# breakout_pmg001.net
KiCad netlist of a schematic drawn in EAGLE
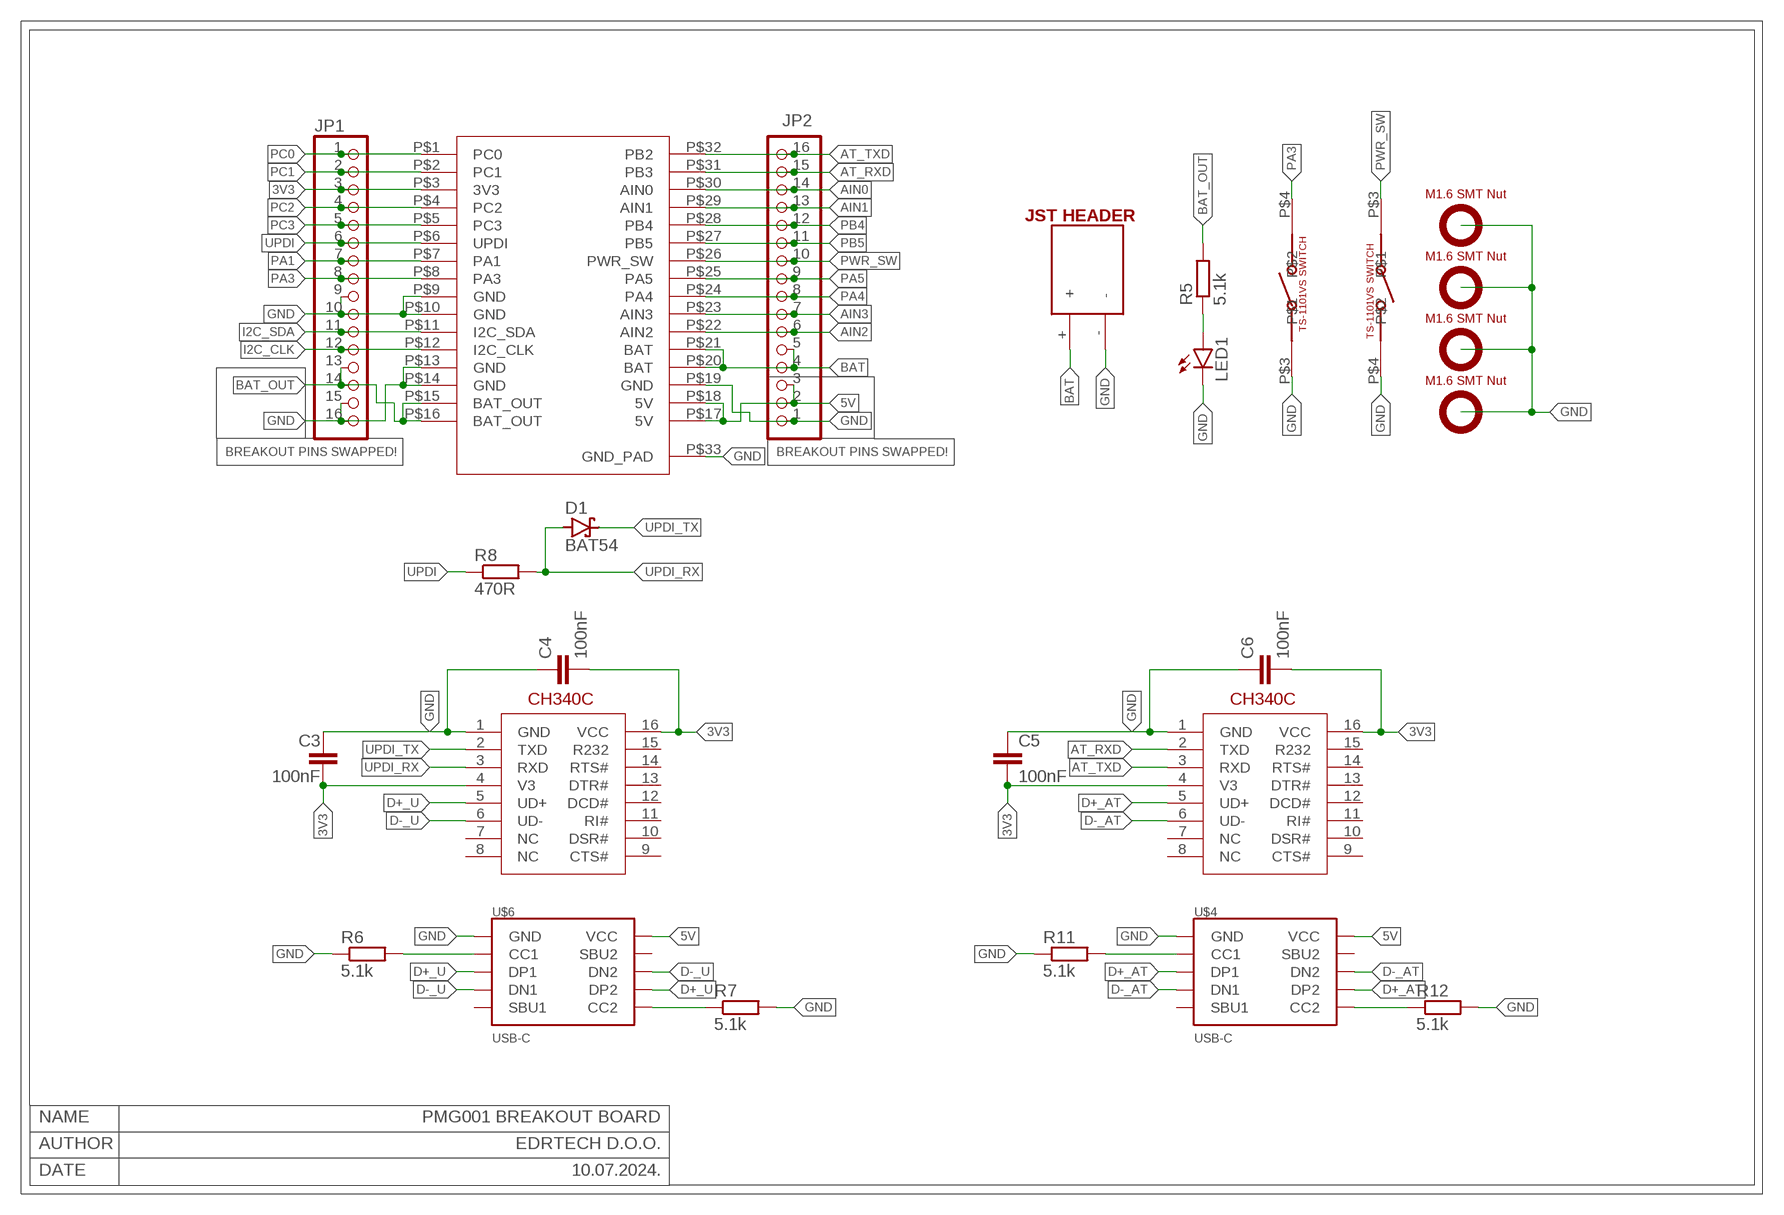
[diagram p0: schematic, sheet 1]

(export (version "E")
  (design (tool "Eeschema 10.0.6"))
  (components
    (comp (ref "C3")
      (value "100nF")
      (footprint "eagle-import:C0603")
      (libsource (lib "eagle-import") (part "CC0603"))
    )
    (comp (ref "C4")
      (value "100nF")
      (footprint "eagle-import:C0603")
      (libsource (lib "eagle-import") (part "CC0603"))
    )
    (comp (ref "C5")
      (value "100nF")
      (footprint "eagle-import:C0603")
      (libsource (lib "eagle-import") (part "CC0603"))
    )
    (comp (ref "C6")
      (value "100nF")
      (footprint "eagle-import:C0603")
      (libsource (lib "eagle-import") (part "CC0603"))
    )
    (comp (ref "D1")
      (value "BAT54")
      (footprint "eagle-import:SOT23")
      (libsource (lib "eagle-import") (part "BAT54"))
    )
    (comp (ref "JP1")
      (value "PINHD-1X16")
      (footprint "eagle-import:1X16")
      (libsource (lib "eagle-import") (part "PINHD-1X16"))
    )
    (comp (ref "JP2")
      (value "PINHD-1X16")
      (footprint "eagle-import:1X16")
      (libsource (lib "eagle-import") (part "PINHD-1X16"))
    )
    (comp (ref "LED1")
      (value "LEDCHIPLED_1206")
      (footprint "eagle-import:CHIPLED_1206")
      (libsource (lib "eagle-import") (part "LEDCHIPLED_1206"))
    )
    (comp (ref "R5")
      (value "5.1k")
      (footprint "eagle-import:R0603")
      (libsource (lib "eagle-import") (part "R-EU_R0603"))
    )
    (comp (ref "R6")
      (value "5.1k")
      (footprint "eagle-import:R0603")
      (libsource (lib "eagle-import") (part "R-EU_R0603"))
    )
    (comp (ref "R7")
      (value "5.1k")
      (footprint "eagle-import:R0603")
      (libsource (lib "eagle-import") (part "R-EU_R0603"))
    )
    (comp (ref "R8")
      (value "470R")
      (footprint "eagle-import:R0603")
      (libsource (lib "eagle-import") (part "R-EU_R0603"))
    )
    (comp (ref "R11")
      (value "5.1k")
      (footprint "eagle-import:R0603")
      (libsource (lib "eagle-import") (part "R-EU_R0603"))
    )
    (comp (ref "R12")
      (value "5.1k")
      (footprint "eagle-import:R0603")
      (libsource (lib "eagle-import") (part "R-EU_R0603"))
    )
    (comp (ref "SPEAKER_CON1")
      (value "JST_HEADER_2MM_2P")
      (footprint "eagle-import:JST_HEADER")
      (libsource (lib "eagle-import") (part "JST_HEADER_2MM_2P"))
    )
    (comp (ref "U$1")
      (value "CH340C")
      (footprint "eagle-import:CH340C")
      (libsource (lib "eagle-import") (part "CH340C"))
    )
    (comp (ref "U$2")
      (value "TS-1101VS-C-A-A")
      (footprint "eagle-import:TS-1101VS-C-A-A")
      (libsource (lib "eagle-import") (part "TS-1101VS-C-A-A"))
    )
    (comp (ref "U$3")
      (value "TS-1101VS-C-A-A")
      (footprint "eagle-import:TS-1101VS-C-A-A")
      (libsource (lib "eagle-import") (part "TS-1101VS-C-A-A"))
    )
    (comp (ref "U$4")
      (value "USB-C")
      (footprint "eagle-import:USB-C")
      (libsource (lib "eagle-import") (part "USB-C"))
    )
    (comp (ref "U$5")
      (value "CH340C")
      (footprint "eagle-import:CH340C")
      (libsource (lib "eagle-import") (part "CH340C"))
    )
    (comp (ref "U$6")
      (value "USB-C")
      (footprint "eagle-import:USB-C")
      (libsource (lib "eagle-import") (part "USB-C"))
    )
    (comp (ref "U$7")
      (value "PMG001")
      (footprint "eagle-import:PMG001")
      (libsource (lib "eagle-import") (part "PMG001"))
    )
    (comp (ref "U$8")
      (value "SMTSO16")
      (footprint "eagle-import:SMTSO16")
      (libsource (lib "eagle-import") (part "SMTSO16"))
    )
    (comp (ref "U$9")
      (value "SMTSO16")
      (footprint "eagle-import:SMTSO16")
      (libsource (lib "eagle-import") (part "SMTSO16"))
    )
    (comp (ref "U$10")
      (value "SMTSO16")
      (footprint "eagle-import:SMTSO16")
      (libsource (lib "eagle-import") (part "SMTSO16"))
    )
    (comp (ref "U$11")
      (value "SMTSO16")
      (footprint "eagle-import:SMTSO16")
      (libsource (lib "eagle-import") (part "SMTSO16"))
    )
  )
  (nets
    (net (code "1") (name "3V3") (class "Default")
      (node (ref "C3") (pin "2") (pinfunction "2_2") (pintype "passive"))
      (node (ref "C4") (pin "2") (pinfunction "2_2") (pintype "passive"))
      (node (ref "C5") (pin "2") (pinfunction "2_2") (pintype "passive"))
      (node (ref "C6") (pin "2") (pinfunction "2_2") (pintype "passive"))
      (node (ref "JP1") (pin "3") (pinfunction "3_3") (pintype "passive"))
      (node (ref "U$1") (pin "16") (pinfunction "VCC_16") (pintype "bidirectional"))
      (node (ref "U$1") (pin "4") (pinfunction "V3_4") (pintype "bidirectional"))
      (node (ref "U$5") (pin "16") (pinfunction "VCC_16") (pintype "bidirectional"))
      (node (ref "U$5") (pin "4") (pinfunction "V3_4") (pintype "bidirectional"))
      (node (ref "U$7") (pin "P$3") (pinfunction "3V3_P$3") (pintype "bidirectional"))
    )
    (net (code "2") (name "5V") (class "Default")
      (node (ref "JP2") (pin "2") (pinfunction "2_2") (pintype "passive"))
      (node (ref "JP2") (pin "3") (pinfunction "3_3") (pintype "passive"))
      (node (ref "U$4") (pin "VCC@1") (pinfunction "VCC_VCC@1") (pintype "bidirectional"))
      (node (ref "U$4") (pin "VCC@2") (pinfunction "VCC_VCC@2") (pintype "bidirectional"))
      (node (ref "U$6") (pin "VCC@1") (pinfunction "VCC_VCC@1") (pintype "bidirectional"))
      (node (ref "U$6") (pin "VCC@2") (pinfunction "VCC_VCC@2") (pintype "bidirectional"))
      (node (ref "U$7") (pin "P$17") (pinfunction "5V_P$17") (pintype "bidirectional"))
      (node (ref "U$7") (pin "P$18") (pinfunction "5V_P$18") (pintype "bidirectional"))
    )
    (net (code "3") (name "AIN0") (class "Default")
      (node (ref "JP2") (pin "14") (pinfunction "14_14") (pintype "passive"))
      (node (ref "U$7") (pin "P$30") (pinfunction "AIN0_P$30") (pintype "bidirectional"))
    )
    (net (code "4") (name "AIN1") (class "Default")
      (node (ref "JP2") (pin "13") (pinfunction "13_13") (pintype "passive"))
      (node (ref "U$7") (pin "P$29") (pinfunction "AIN1_P$29") (pintype "bidirectional"))
    )
    (net (code "5") (name "AIN2") (class "Default")
      (node (ref "JP2") (pin "6") (pinfunction "6_6") (pintype "passive"))
      (node (ref "U$7") (pin "P$22") (pinfunction "AIN2_P$22") (pintype "bidirectional"))
    )
    (net (code "6") (name "AIN3") (class "Default")
      (node (ref "JP2") (pin "7") (pinfunction "7_7") (pintype "passive"))
      (node (ref "U$7") (pin "P$23") (pinfunction "AIN3_P$23") (pintype "bidirectional"))
    )
    (net (code "7") (name "AT_RXD") (class "Default")
      (node (ref "JP2") (pin "15") (pinfunction "15_15") (pintype "passive"))
      (node (ref "U$1") (pin "2") (pinfunction "TXD_2") (pintype "bidirectional"))
      (node (ref "U$7") (pin "P$31") (pinfunction "PB3_P$31") (pintype "bidirectional"))
    )
    (net (code "8") (name "AT_TXD") (class "Default")
      (node (ref "JP2") (pin "16") (pinfunction "16_16") (pintype "passive"))
      (node (ref "U$1") (pin "3") (pinfunction "RXD_3") (pintype "bidirectional"))
      (node (ref "U$7") (pin "P$32") (pinfunction "PB2_P$32") (pintype "bidirectional"))
    )
    (net (code "9") (name "BAT") (class "Default")
      (node (ref "JP2") (pin "4") (pinfunction "4_4") (pintype "passive"))
      (node (ref "JP2") (pin "5") (pinfunction "5_5") (pintype "passive"))
      (node (ref "SPEAKER_CON1") (pin "+") (pinfunction "+_+") (pintype "bidirectional"))
      (node (ref "U$7") (pin "P$20") (pinfunction "BAT_P$20") (pintype "bidirectional"))
      (node (ref "U$7") (pin "P$21") (pinfunction "BAT_P$21") (pintype "bidirectional"))
    )
    (net (code "10") (name "BAT_OUT") (class "Default")
      (node (ref "JP1") (pin "13") (pinfunction "13_13") (pintype "passive"))
      (node (ref "JP1") (pin "14") (pinfunction "14_14") (pintype "passive"))
      (node (ref "R5") (pin "2") (pinfunction "2_2") (pintype "passive"))
      (node (ref "U$7") (pin "P$15") (pinfunction "BAT_OUT_P$15") (pintype "bidirectional"))
      (node (ref "U$7") (pin "P$16") (pinfunction "BAT_OUT_P$16") (pintype "bidirectional"))
    )
    (net (code "11") (name "D+_AT") (class "Default")
      (node (ref "U$1") (pin "5") (pinfunction "UD+_5") (pintype "bidirectional"))
      (node (ref "U$4") (pin "DP1") (pinfunction "DP1_DP1") (pintype "bidirectional"))
      (node (ref "U$4") (pin "DP2") (pinfunction "DP2_DP2") (pintype "bidirectional"))
    )
    (net (code "12") (name "D+_U") (class "Default")
      (node (ref "U$5") (pin "5") (pinfunction "UD+_5") (pintype "bidirectional"))
      (node (ref "U$6") (pin "DP1") (pinfunction "DP1_DP1") (pintype "bidirectional"))
      (node (ref "U$6") (pin "DP2") (pinfunction "DP2_DP2") (pintype "bidirectional"))
    )
    (net (code "13") (name "D-_AT") (class "Default")
      (node (ref "U$1") (pin "6") (pinfunction "UD-_6") (pintype "bidirectional"))
      (node (ref "U$4") (pin "DN1") (pinfunction "DN1_DN1") (pintype "bidirectional"))
      (node (ref "U$4") (pin "DN2") (pinfunction "DN2_DN2") (pintype "bidirectional"))
    )
    (net (code "14") (name "D-_U") (class "Default")
      (node (ref "U$5") (pin "6") (pinfunction "UD-_6") (pintype "bidirectional"))
      (node (ref "U$6") (pin "DN1") (pinfunction "DN1_DN1") (pintype "bidirectional"))
      (node (ref "U$6") (pin "DN2") (pinfunction "DN2_DN2") (pintype "bidirectional"))
    )
    (net (code "15") (name "GND") (class "Default")
      (node (ref "C3") (pin "1") (pinfunction "1_1") (pintype "passive"))
      (node (ref "C4") (pin "1") (pinfunction "1_1") (pintype "passive"))
      (node (ref "C5") (pin "1") (pinfunction "1_1") (pintype "passive"))
      (node (ref "C6") (pin "1") (pinfunction "1_1") (pintype "passive"))
      (node (ref "JP1") (pin "10") (pinfunction "10_10") (pintype "passive"))
      (node (ref "JP1") (pin "15") (pinfunction "15_15") (pintype "passive"))
      (node (ref "JP1") (pin "16") (pinfunction "16_16") (pintype "passive"))
      (node (ref "JP1") (pin "9") (pinfunction "9_9") (pintype "passive"))
      (node (ref "JP2") (pin "1") (pinfunction "1_1") (pintype "passive"))
      (node (ref "LED1") (pin "C") (pinfunction "C_C") (pintype "passive"))
      (node (ref "R11") (pin "1") (pinfunction "1_1") (pintype "passive"))
      (node (ref "R12") (pin "2") (pinfunction "2_2") (pintype "passive"))
      (node (ref "R6") (pin "1") (pinfunction "1_1") (pintype "passive"))
      (node (ref "R7") (pin "2") (pinfunction "2_2") (pintype "passive"))
      (node (ref "SPEAKER_CON1") (pin "-") (pinfunction "-_-") (pintype "bidirectional"))
      (node (ref "U$1") (pin "1") (pinfunction "GND_1") (pintype "bidirectional"))
      (node (ref "U$10") (pin "P$1") (pinfunction "P$1_P$1") (pintype "bidirectional"))
      (node (ref "U$11") (pin "P$1") (pinfunction "P$1_P$1") (pintype "bidirectional"))
      (node (ref "U$2") (pin "P$3") (pinfunction "P$1_P$3") (pintype "bidirectional"))
      (node (ref "U$3") (pin "P$4") (pinfunction "P$2_P$4") (pintype "bidirectional"))
      (node (ref "U$4") (pin "GND@1") (pinfunction "GND_GND@1") (pintype "bidirectional"))
      (node (ref "U$4") (pin "GND@2") (pinfunction "GND_GND@2") (pintype "bidirectional"))
      (node (ref "U$4") (pin "P$1") (pinfunction "GND_P$1") (pintype "bidirectional"))
      (node (ref "U$4") (pin "P$2") (pinfunction "GND_P$2") (pintype "bidirectional"))
      (node (ref "U$4") (pin "P$3") (pinfunction "GND_P$3") (pintype "bidirectional"))
      (node (ref "U$4") (pin "P$4") (pinfunction "GND_P$4") (pintype "bidirectional"))
      (node (ref "U$5") (pin "1") (pinfunction "GND_1") (pintype "bidirectional"))
      (node (ref "U$6") (pin "GND@1") (pinfunction "GND_GND@1") (pintype "bidirectional"))
      (node (ref "U$6") (pin "GND@2") (pinfunction "GND_GND@2") (pintype "bidirectional"))
      (node (ref "U$6") (pin "P$1") (pinfunction "GND_P$1") (pintype "bidirectional"))
      (node (ref "U$6") (pin "P$2") (pinfunction "GND_P$2") (pintype "bidirectional"))
      (node (ref "U$6") (pin "P$3") (pinfunction "GND_P$3") (pintype "bidirectional"))
      (node (ref "U$6") (pin "P$4") (pinfunction "GND_P$4") (pintype "bidirectional"))
      (node (ref "U$7") (pin "P$10") (pinfunction "GND_P$10") (pintype "bidirectional"))
      (node (ref "U$7") (pin "P$13") (pinfunction "GND_P$13") (pintype "bidirectional"))
      (node (ref "U$7") (pin "P$14") (pinfunction "GND_P$14") (pintype "bidirectional"))
      (node (ref "U$7") (pin "P$19") (pinfunction "GND_P$19") (pintype "bidirectional"))
      (node (ref "U$7") (pin "P$33") (pinfunction "GND_PAD_P$33") (pintype "bidirectional"))
      (node (ref "U$7") (pin "P$9") (pinfunction "GND_P$9") (pintype "bidirectional"))
      (node (ref "U$8") (pin "P$1") (pinfunction "P$1_P$1") (pintype "bidirectional"))
      (node (ref "U$9") (pin "P$1") (pinfunction "P$1_P$1") (pintype "bidirectional"))
    )
    (net (code "16") (name "I2C_CLK") (class "Default")
      (node (ref "JP1") (pin "12") (pinfunction "12_12") (pintype "passive"))
      (node (ref "U$7") (pin "P$12") (pinfunction "I2C_CLK_P$12") (pintype "bidirectional"))
    )
    (net (code "17") (name "I2C_SDA") (class "Default")
      (node (ref "JP1") (pin "11") (pinfunction "11_11") (pintype "passive"))
      (node (ref "U$7") (pin "P$11") (pinfunction "I2C_SDA_P$11") (pintype "bidirectional"))
    )
    (net (code "18") (name "Net-(LED1-PadA)") (class "Default")
      (node (ref "LED1") (pin "A") (pinfunction "A_A") (pintype "passive"))
      (node (ref "R5") (pin "1") (pinfunction "1_1") (pintype "passive"))
    )
    (net (code "19") (name "Net-(R6-Pad2)") (class "Default")
      (node (ref "R6") (pin "2") (pinfunction "2_2") (pintype "passive"))
      (node (ref "U$6") (pin "CC1") (pinfunction "CC1_CC1") (pintype "bidirectional"))
    )
    (net (code "20") (name "Net-(R7-Pad1)") (class "Default")
      (node (ref "R7") (pin "1") (pinfunction "1_1") (pintype "passive"))
      (node (ref "U$6") (pin "CC2") (pinfunction "CC2_CC2") (pintype "bidirectional"))
    )
    (net (code "21") (name "Net-(R11-Pad2)") (class "Default")
      (node (ref "R11") (pin "2") (pinfunction "2_2") (pintype "passive"))
      (node (ref "U$4") (pin "CC1") (pinfunction "CC1_CC1") (pintype "bidirectional"))
    )
    (net (code "22") (name "Net-(R12-Pad1)") (class "Default")
      (node (ref "R12") (pin "1") (pinfunction "1_1") (pintype "passive"))
      (node (ref "U$4") (pin "CC2") (pinfunction "CC2_CC2") (pintype "bidirectional"))
    )
    (net (code "23") (name "PA1") (class "Default")
      (node (ref "JP1") (pin "7") (pinfunction "7_7") (pintype "passive"))
      (node (ref "U$7") (pin "P$7") (pinfunction "PA1_P$7") (pintype "bidirectional"))
    )
    (net (code "24") (name "PA3") (class "Default")
      (node (ref "JP1") (pin "8") (pinfunction "8_8") (pintype "passive"))
      (node (ref "U$2") (pin "P$4") (pinfunction "P$2_P$4") (pintype "bidirectional"))
      (node (ref "U$7") (pin "P$8") (pinfunction "PA3_P$8") (pintype "bidirectional"))
    )
    (net (code "25") (name "PA4") (class "Default")
      (node (ref "JP2") (pin "8") (pinfunction "8_8") (pintype "passive"))
      (node (ref "U$7") (pin "P$24") (pinfunction "PA4_P$24") (pintype "bidirectional"))
    )
    (net (code "26") (name "PA5") (class "Default")
      (node (ref "JP2") (pin "9") (pinfunction "9_9") (pintype "passive"))
      (node (ref "U$7") (pin "P$25") (pinfunction "PA5_P$25") (pintype "bidirectional"))
    )
    (net (code "27") (name "PB4") (class "Default")
      (node (ref "JP2") (pin "12") (pinfunction "12_12") (pintype "passive"))
      (node (ref "U$7") (pin "P$28") (pinfunction "PB4_P$28") (pintype "bidirectional"))
    )
    (net (code "28") (name "PB5") (class "Default")
      (node (ref "JP2") (pin "11") (pinfunction "11_11") (pintype "passive"))
      (node (ref "U$7") (pin "P$27") (pinfunction "PB5_P$27") (pintype "bidirectional"))
    )
    (net (code "29") (name "PC0") (class "Default")
      (node (ref "JP1") (pin "1") (pinfunction "1_1") (pintype "passive"))
      (node (ref "U$7") (pin "P$1") (pinfunction "PC0_P$1") (pintype "bidirectional"))
    )
    (net (code "30") (name "PC1") (class "Default")
      (node (ref "JP1") (pin "2") (pinfunction "2_2") (pintype "passive"))
      (node (ref "U$7") (pin "P$2") (pinfunction "PC1_P$2") (pintype "bidirectional"))
    )
    (net (code "31") (name "PC2") (class "Default")
      (node (ref "JP1") (pin "4") (pinfunction "4_4") (pintype "passive"))
      (node (ref "U$7") (pin "P$4") (pinfunction "PC2_P$4") (pintype "bidirectional"))
    )
    (net (code "32") (name "PC3") (class "Default")
      (node (ref "JP1") (pin "5") (pinfunction "5_5") (pintype "passive"))
      (node (ref "U$7") (pin "P$5") (pinfunction "PC3_P$5") (pintype "bidirectional"))
    )
    (net (code "33") (name "PWR_SW") (class "Default")
      (node (ref "JP2") (pin "10") (pinfunction "10_10") (pintype "passive"))
      (node (ref "U$3") (pin "P$3") (pinfunction "P$1_P$3") (pintype "bidirectional"))
      (node (ref "U$7") (pin "P$26") (pinfunction "PWR_SW_P$26") (pintype "bidirectional"))
    )
    (net (code "34") (name "UPDI") (class "Default")
      (node (ref "JP1") (pin "6") (pinfunction "6_6") (pintype "passive"))
      (node (ref "R8") (pin "1") (pinfunction "1_1") (pintype "passive"))
      (node (ref "U$7") (pin "P$6") (pinfunction "UPDI_P$6") (pintype "bidirectional"))
    )
    (net (code "35") (name "UPDI_RX") (class "Default")
      (node (ref "D1") (pin "1") (pinfunction "A_1") (pintype "passive"))
      (node (ref "R8") (pin "2") (pinfunction "2_2") (pintype "passive"))
      (node (ref "U$5") (pin "3") (pinfunction "RXD_3") (pintype "bidirectional"))
    )
    (net (code "36") (name "UPDI_TX") (class "Default")
      (node (ref "D1") (pin "3") (pinfunction "C_3") (pintype "passive"))
      (node (ref "U$5") (pin "2") (pinfunction "TXD_2") (pintype "bidirectional"))
    )
    (net (code "37") (name "unconnected-(U$1-CTS#-Pad9)") (class "Default")
      (node (ref "U$1") (pin "9") (pinfunction "CTS#_9") (pintype "bidirectional"))
    )
    (net (code "38") (name "unconnected-(U$1-DCD#-Pad12)") (class "Default")
      (node (ref "U$1") (pin "12") (pinfunction "DCD#_12") (pintype "bidirectional"))
    )
    (net (code "39") (name "unconnected-(U$1-DSR#-Pad10)") (class "Default")
      (node (ref "U$1") (pin "10") (pinfunction "DSR#_10") (pintype "bidirectional"))
    )
    (net (code "40") (name "unconnected-(U$1-DTR#-Pad13)") (class "Default")
      (node (ref "U$1") (pin "13") (pinfunction "DTR#_13") (pintype "bidirectional"))
    )
    (net (code "41") (name "unconnected-(U$1-NC-Pad7)") (class "Default")
      (node (ref "U$1") (pin "7") (pinfunction "NC_7") (pintype "bidirectional"))
    )
    (net (code "42") (name "unconnected-(U$1-NC-Pad8)") (class "Default")
      (node (ref "U$1") (pin "8") (pinfunction "NC_8") (pintype "bidirectional"))
    )
    (net (code "43") (name "unconnected-(U$1-R232-Pad15)") (class "Default")
      (node (ref "U$1") (pin "15") (pinfunction "R232_15") (pintype "bidirectional"))
    )
    (net (code "44") (name "unconnected-(U$1-RI#-Pad11)") (class "Default")
      (node (ref "U$1") (pin "11") (pinfunction "RI#_11") (pintype "bidirectional"))
    )
    (net (code "45") (name "unconnected-(U$1-RTS#-Pad14)") (class "Default")
      (node (ref "U$1") (pin "14") (pinfunction "RTS#_14") (pintype "bidirectional"))
    )
    (net (code "46") (name "unconnected-(U$4-PadSBU1)") (class "Default")
      (node (ref "U$4") (pin "SBU1") (pinfunction "SBU1_SBU1") (pintype "bidirectional"))
    )
    (net (code "47") (name "unconnected-(U$4-PadSBU2)") (class "Default")
      (node (ref "U$4") (pin "SBU2") (pinfunction "SBU2_SBU2") (pintype "bidirectional"))
    )
    (net (code "48") (name "unconnected-(U$5-CTS#-Pad9)") (class "Default")
      (node (ref "U$5") (pin "9") (pinfunction "CTS#_9") (pintype "bidirectional"))
    )
    (net (code "49") (name "unconnected-(U$5-DCD#-Pad12)") (class "Default")
      (node (ref "U$5") (pin "12") (pinfunction "DCD#_12") (pintype "bidirectional"))
    )
    (net (code "50") (name "unconnected-(U$5-DSR#-Pad10)") (class "Default")
      (node (ref "U$5") (pin "10") (pinfunction "DSR#_10") (pintype "bidirectional"))
    )
    (net (code "51") (name "unconnected-(U$5-DTR#-Pad13)") (class "Default")
      (node (ref "U$5") (pin "13") (pinfunction "DTR#_13") (pintype "bidirectional"))
    )
    (net (code "52") (name "unconnected-(U$5-NC-Pad7)") (class "Default")
      (node (ref "U$5") (pin "7") (pinfunction "NC_7") (pintype "bidirectional"))
    )
    (net (code "53") (name "unconnected-(U$5-NC-Pad8)") (class "Default")
      (node (ref "U$5") (pin "8") (pinfunction "NC_8") (pintype "bidirectional"))
    )
    (net (code "54") (name "unconnected-(U$5-R232-Pad15)") (class "Default")
      (node (ref "U$5") (pin "15") (pinfunction "R232_15") (pintype "bidirectional"))
    )
    (net (code "55") (name "unconnected-(U$5-RI#-Pad11)") (class "Default")
      (node (ref "U$5") (pin "11") (pinfunction "RI#_11") (pintype "bidirectional"))
    )
    (net (code "56") (name "unconnected-(U$5-RTS#-Pad14)") (class "Default")
      (node (ref "U$5") (pin "14") (pinfunction "RTS#_14") (pintype "bidirectional"))
    )
    (net (code "57") (name "unconnected-(U$6-PadSBU1)") (class "Default")
      (node (ref "U$6") (pin "SBU1") (pinfunction "SBU1_SBU1") (pintype "bidirectional"))
    )
    (net (code "58") (name "unconnected-(U$6-PadSBU2)") (class "Default")
      (node (ref "U$6") (pin "SBU2") (pinfunction "SBU2_SBU2") (pintype "bidirectional"))
    )
  )
)
